# ADNS-9800.net
KiCad netlist of a schematic drawn in EAGLE
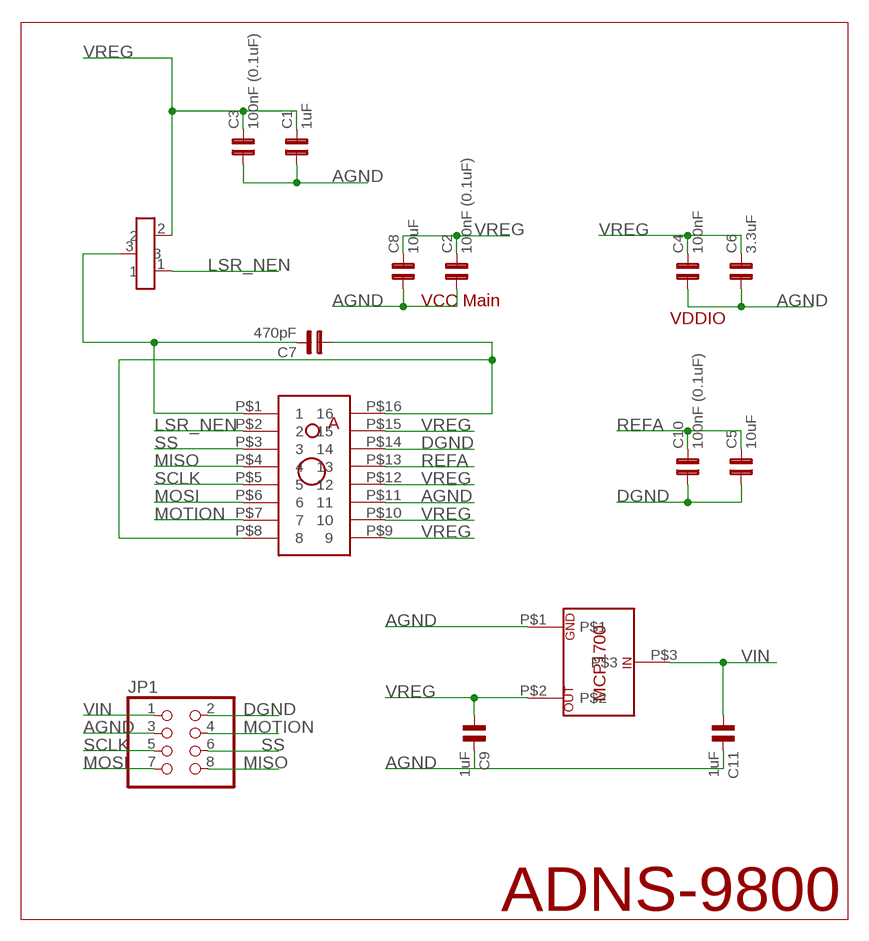
[diagram p0: schematic, sheet 1]

(export (version "E")
  (design (tool "Eeschema 10.0.6"))
  (components
    (comp (ref "C1")
      (value "1uF")
      (footprint "eagle-import:0603")
      (libsource (lib "eagle-import") (part "C0603"))
    )
    (comp (ref "C2")
      (value "100nF (0.1uF)")
      (footprint "eagle-import:0603")
      (libsource (lib "eagle-import") (part "C0603"))
    )
    (comp (ref "C3")
      (value "100nF (0.1uF)")
      (footprint "eagle-import:0603")
      (libsource (lib "eagle-import") (part "C0603"))
    )
    (comp (ref "C4")
      (value "100nF")
      (footprint "eagle-import:0603")
      (libsource (lib "eagle-import") (part "C0603"))
    )
    (comp (ref "C5")
      (value "10uF")
      (footprint "eagle-import:0603")
      (libsource (lib "eagle-import") (part "C0603"))
    )
    (comp (ref "C6")
      (value "3.3uF")
      (footprint "eagle-import:0603")
      (libsource (lib "eagle-import") (part "C0603"))
    )
    (comp (ref "C7")
      (value "470pF")
      (footprint "eagle-import:0603")
      (libsource (lib "eagle-import") (part "C0603"))
    )
    (comp (ref "C8")
      (value "10uF")
      (footprint "eagle-import:0603")
      (libsource (lib "eagle-import") (part "C0603"))
    )
    (comp (ref "C9")
      (value "1uF")
      (footprint "eagle-import:0603")
      (libsource (lib "eagle-import") (part "C0603"))
    )
    (comp (ref "C10")
      (value "100nF (0.1uF)")
      (footprint "eagle-import:0603")
      (libsource (lib "eagle-import") (part "C0603"))
    )
    (comp (ref "C11")
      (value "1uF")
      (footprint "eagle-import:0603")
      (libsource (lib "eagle-import") (part "C0603"))
    )
    (comp (ref "JP1")
      (value "PINHD-2X4")
      (footprint "eagle-import:2X04")
      (libsource (lib "eagle-import") (part "PINHD-2X4"))
    )
    (comp (ref "Q1")
      (value "TRANSISTOR_SC-75")
      (footprint "eagle-import:SC-75_TRANSISTOR")
      (libsource (lib "eagle-import") (part "TRANSISTOR_SC-75"))
    )
    (comp (ref "U$1")
      (value "AVAGO_ADNS-9500")
      (footprint "eagle-import:AVAGO_ADNS-9500")
      (libsource (lib "eagle-import") (part "AVAGO_ADNS-9500"))
    )
    (comp (ref "U$2")
      (value "MCP1700__LDO")
      (footprint "eagle-import:MCP1700__LDO")
      (libsource (lib "eagle-import") (part "MCP1700__LDO"))
    )
  )
  (nets
    (net (code "1") (name "/AGND") (class "Default")
      (node (ref "C1") (pin "1") (pinfunction "1_1") (pintype "passive"))
      (node (ref "C11") (pin "2") (pinfunction "2_2") (pintype "passive"))
      (node (ref "C2") (pin "1") (pinfunction "1_1") (pintype "passive"))
      (node (ref "C3") (pin "1") (pinfunction "1_1") (pintype "passive"))
      (node (ref "C4") (pin "1") (pinfunction "1_1") (pintype "passive"))
      (node (ref "C6") (pin "1") (pinfunction "1_1") (pintype "passive"))
      (node (ref "C8") (pin "1") (pinfunction "1_1") (pintype "passive"))
      (node (ref "C9") (pin "2") (pinfunction "2_2") (pintype "passive"))
      (node (ref "JP1") (pin "3") (pinfunction "3_3") (pintype "passive"))
      (node (ref "U$1") (pin "P$11") (pinfunction "11_P$11") (pintype "bidirectional"))
      (node (ref "U$2") (pin "P$1") (pinfunction "P$1_P$1") (pintype "bidirectional"))
    )
    (net (code "2") (name "/DGND") (class "Default")
      (node (ref "C10") (pin "1") (pinfunction "1_1") (pintype "passive"))
      (node (ref "C5") (pin "1") (pinfunction "1_1") (pintype "passive"))
      (node (ref "JP1") (pin "2") (pinfunction "2_2") (pintype "passive"))
      (node (ref "U$1") (pin "P$14") (pinfunction "14_P$14") (pintype "bidirectional"))
    )
    (net (code "3") (name "/LSR_NEN") (class "Default")
      (node (ref "Q1") (pin "1") (pinfunction "1_1") (pintype "bidirectional"))
      (node (ref "U$1") (pin "P$2") (pinfunction "2_P$2") (pintype "bidirectional"))
    )
    (net (code "4") (name "/MISO") (class "Default")
      (node (ref "JP1") (pin "8") (pinfunction "8_8") (pintype "passive"))
      (node (ref "U$1") (pin "P$4") (pinfunction "4_P$4") (pintype "bidirectional"))
    )
    (net (code "5") (name "/MOSI") (class "Default")
      (node (ref "JP1") (pin "7") (pinfunction "7_7") (pintype "passive"))
      (node (ref "U$1") (pin "P$6") (pinfunction "6_P$6") (pintype "bidirectional"))
    )
    (net (code "6") (name "/MOTION") (class "Default")
      (node (ref "JP1") (pin "4") (pinfunction "4_4") (pintype "passive"))
      (node (ref "U$1") (pin "P$7") (pinfunction "7_P$7") (pintype "bidirectional"))
    )
    (net (code "7") (name "/REFA") (class "Default")
      (node (ref "C10") (pin "2") (pinfunction "2_2") (pintype "passive"))
      (node (ref "C5") (pin "2") (pinfunction "2_2") (pintype "passive"))
      (node (ref "U$1") (pin "P$13") (pinfunction "13_P$13") (pintype "bidirectional"))
    )
    (net (code "8") (name "/SCLK") (class "Default")
      (node (ref "JP1") (pin "5") (pinfunction "5_5") (pintype "passive"))
      (node (ref "U$1") (pin "P$5") (pinfunction "5_P$5") (pintype "bidirectional"))
    )
    (net (code "9") (name "/SS") (class "Default")
      (node (ref "JP1") (pin "6") (pinfunction "6_6") (pintype "passive"))
      (node (ref "U$1") (pin "P$3") (pinfunction "3_P$3") (pintype "bidirectional"))
    )
    (net (code "10") (name "/VIN") (class "Default")
      (node (ref "C11") (pin "1") (pinfunction "1_1") (pintype "passive"))
      (node (ref "JP1") (pin "1") (pinfunction "1_1") (pintype "passive"))
      (node (ref "U$2") (pin "P$3") (pinfunction "P$3_P$3") (pintype "bidirectional"))
    )
    (net (code "11") (name "/VREG") (class "Default")
      (node (ref "C1") (pin "2") (pinfunction "2_2") (pintype "passive"))
      (node (ref "C2") (pin "2") (pinfunction "2_2") (pintype "passive"))
      (node (ref "C3") (pin "2") (pinfunction "2_2") (pintype "passive"))
      (node (ref "C4") (pin "2") (pinfunction "2_2") (pintype "passive"))
      (node (ref "C6") (pin "2") (pinfunction "2_2") (pintype "passive"))
      (node (ref "C8") (pin "2") (pinfunction "2_2") (pintype "passive"))
      (node (ref "C9") (pin "1") (pinfunction "1_1") (pintype "passive"))
      (node (ref "Q1") (pin "2") (pinfunction "2_2") (pintype "bidirectional"))
      (node (ref "U$1") (pin "P$10") (pinfunction "10_P$10") (pintype "bidirectional"))
      (node (ref "U$1") (pin "P$12") (pinfunction "12_P$12") (pintype "bidirectional"))
      (node (ref "U$1") (pin "P$15") (pinfunction "15_P$15") (pintype "bidirectional"))
      (node (ref "U$1") (pin "P$9") (pinfunction "9_P$9") (pintype "bidirectional"))
      (node (ref "U$2") (pin "P$2") (pinfunction "P$2_P$2") (pintype "bidirectional"))
    )
    (net (code "12") (name "Net-(U$1-1)") (class "Default")
      (node (ref "C7") (pin "2") (pinfunction "2_2") (pintype "passive"))
      (node (ref "Q1") (pin "3") (pinfunction "3_3") (pintype "bidirectional"))
      (node (ref "U$1") (pin "P$1") (pinfunction "1_P$1") (pintype "bidirectional"))
    )
    (net (code "13") (name "Net-(U$1-16)") (class "Default")
      (node (ref "C7") (pin "1") (pinfunction "1_1") (pintype "passive"))
      (node (ref "U$1") (pin "P$16") (pinfunction "16_P$16") (pintype "bidirectional"))
      (node (ref "U$1") (pin "P$8") (pinfunction "8_P$8") (pintype "bidirectional"))
    )
  )
)
